# 02-MCU.net
KiCad netlist of a schematic drawn in Altium Designer
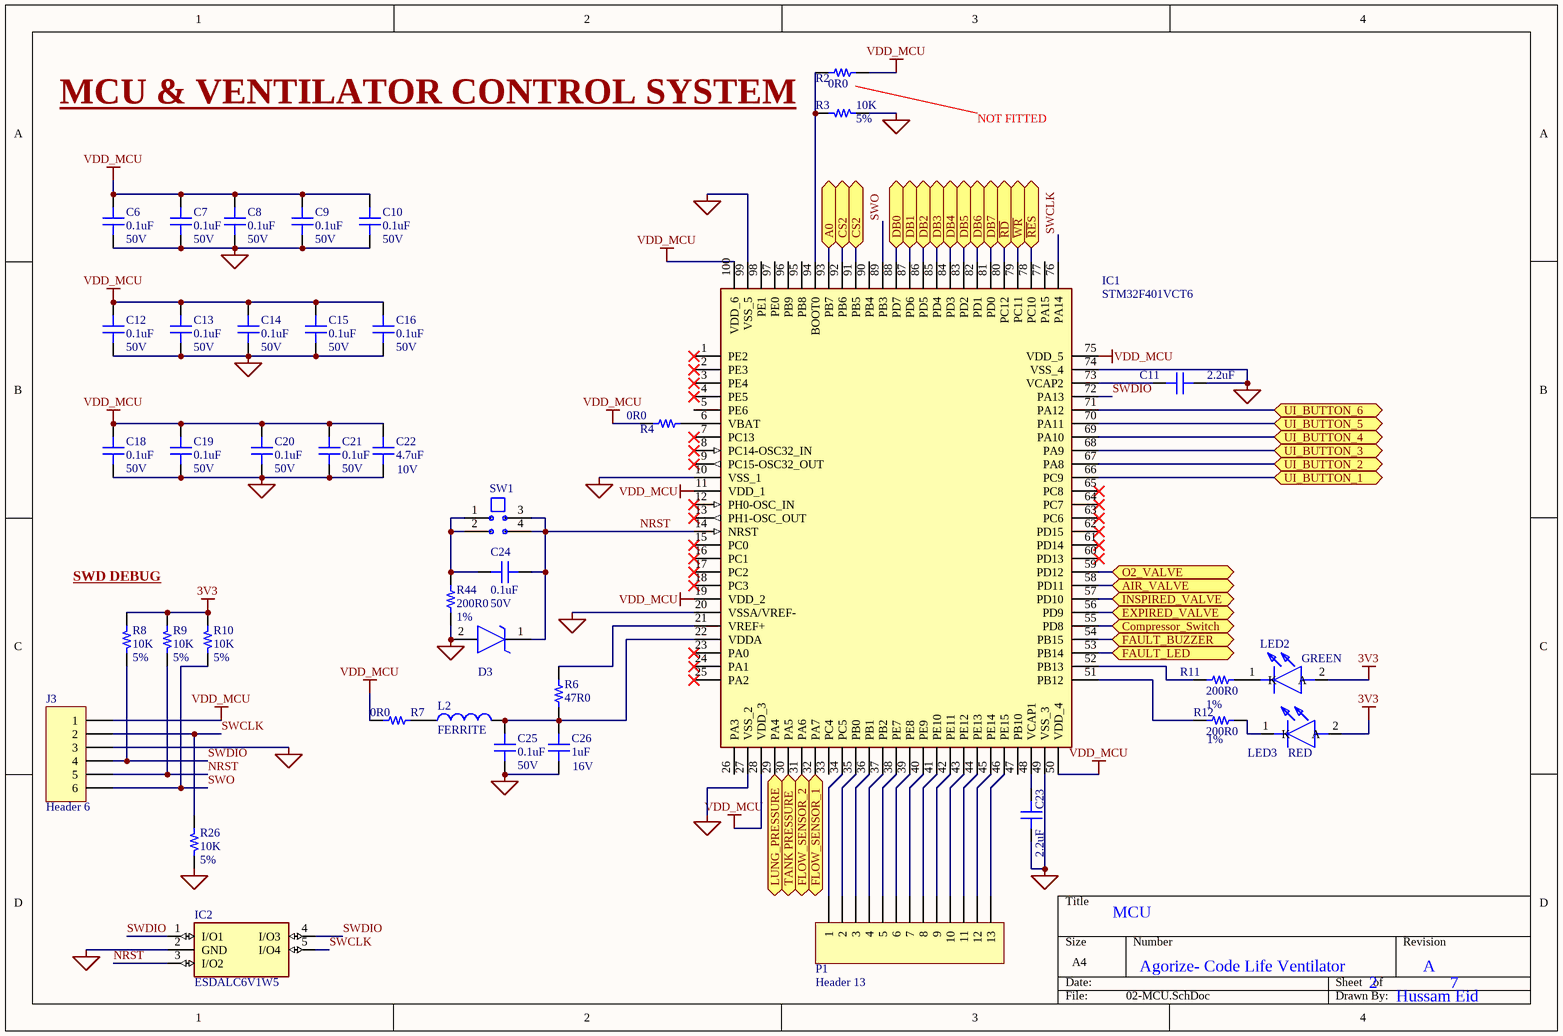
[diagram p0: 02-MCU.SchDoc]

(export (version "E")
  (design (tool "Eeschema 10.0.6"))
  (components
    (comp (ref "C6")
      (value "0.1uF")
      (footprint "CAP 0603/1608")
      (description "CAP CER 0.1UF 50V X7R 0603")
      (fields (field (name "TOLERANCE") "20%") (field (name "VOLTAGE RATING") "50V"))
      (libsource (lib "Celestial Library Database") (part "Capacitor"))
    )
    (comp (ref "C7")
      (value "0.1uF")
      (footprint "CAP 0603/1608")
      (description "CAP CER 0.1UF 50V X7R 0603")
      (fields (field (name "TOLERANCE") "20%") (field (name "VOLTAGE RATING") "50V"))
      (libsource (lib "Celestial Library Database") (part "Capacitor"))
    )
    (comp (ref "C8")
      (value "0.1uF")
      (footprint "CAP 0603/1608")
      (description "CAP CER 0.1UF 50V X7R 0603")
      (fields (field (name "TOLERANCE") "20%") (field (name "VOLTAGE RATING") "50V"))
      (libsource (lib "Celestial Library Database") (part "Capacitor"))
    )
    (comp (ref "C9")
      (value "0.1uF")
      (footprint "CAP 0603/1608")
      (description "CAP CER 0.1UF 50V X7R 0603")
      (fields (field (name "TOLERANCE") "20%") (field (name "VOLTAGE RATING") "50V"))
      (libsource (lib "Celestial Library Database") (part "Capacitor"))
    )
    (comp (ref "C10")
      (value "0.1uF")
      (footprint "CAP 0603/1608")
      (description "CAP CER 0.1UF 50V X7R 0603")
      (fields (field (name "TOLERANCE") "20%") (field (name "VOLTAGE RATING") "50V"))
      (libsource (lib "Celestial Library Database") (part "Capacitor"))
    )
    (comp (ref "C11")
      (value "2.2uF")
      (footprint "CAP 0603/1608")
      (description "CAP CER 2.2UF 16V X5R 0603")
      (fields (field (name "TOLERANCE") "10%") (field (name "VOLTAGE") "16V"))
      (libsource (lib "Celestial Library Database") (part "Capacitor"))
    )
    (comp (ref "C12")
      (value "0.1uF")
      (footprint "CAP 0603/1608")
      (description "CAP CER 0.1UF 50V X7R 0603")
      (fields (field (name "TOLERANCE") "20%") (field (name "VOLTAGE RATING") "50V"))
      (libsource (lib "Celestial Library Database") (part "Capacitor"))
    )
    (comp (ref "C13")
      (value "0.1uF")
      (footprint "CAP 0603/1608")
      (description "CAP CER 0.1UF 50V X7R 0603")
      (fields (field (name "TOLERANCE") "20%") (field (name "VOLTAGE RATING") "50V"))
      (libsource (lib "Celestial Library Database") (part "Capacitor"))
    )
    (comp (ref "C14")
      (value "0.1uF")
      (footprint "CAP 0603/1608")
      (description "CAP CER 0.1UF 50V X7R 0603")
      (fields (field (name "TOLERANCE") "20%") (field (name "VOLTAGE RATING") "50V"))
      (libsource (lib "Celestial Library Database") (part "Capacitor"))
    )
    (comp (ref "C15")
      (value "0.1uF")
      (footprint "CAP 0603/1608")
      (description "CAP CER 0.1UF 50V X7R 0603")
      (fields (field (name "TOLERANCE") "20%") (field (name "VOLTAGE RATING") "50V"))
      (libsource (lib "Celestial Library Database") (part "Capacitor"))
    )
    (comp (ref "C16")
      (value "0.1uF")
      (footprint "CAP 0603/1608")
      (description "CAP CER 0.1UF 50V X7R 0603")
      (fields (field (name "TOLERANCE") "20%") (field (name "VOLTAGE RATING") "50V"))
      (libsource (lib "Celestial Library Database") (part "Capacitor"))
    )
    (comp (ref "C18")
      (value "0.1uF")
      (footprint "CAP 0603/1608")
      (description "CAP CER 0.1UF 50V X7R 0603")
      (fields (field (name "TOLERANCE") "20%") (field (name "VOLTAGE RATING") "50V"))
      (libsource (lib "Celestial Library Database") (part "Capacitor"))
    )
    (comp (ref "C19")
      (value "0.1uF")
      (footprint "CAP 0603/1608")
      (description "CAP CER 0.1UF 50V X7R 0603")
      (fields (field (name "TOLERANCE") "20%") (field (name "VOLTAGE RATING") "50V"))
      (libsource (lib "Celestial Library Database") (part "Capacitor"))
    )
    (comp (ref "C20")
      (value "0.1uF")
      (footprint "CAP 0603/1608")
      (description "CAP CER 0.1UF 50V X7R 0603")
      (fields (field (name "TOLERANCE") "20%") (field (name "VOLTAGE RATING") "50V"))
      (libsource (lib "Celestial Library Database") (part "Capacitor"))
    )
    (comp (ref "C21")
      (value "0.1uF")
      (footprint "CAP 0603/1608")
      (description "CAP CER 0.1UF 50V X7R 0603")
      (fields (field (name "TOLERANCE") "20%") (field (name "VOLTAGE RATING") "50V"))
      (libsource (lib "Celestial Library Database") (part "Capacitor"))
    )
    (comp (ref "C22")
      (value "4.7uF")
      (footprint "CAP 0603/1608")
      (description "CAP CER 4.7UF 10V X5R 0603")
      (fields (field (name "TOLERANCE") "10%") (field (name "VOLTAGE RATING") "10V"))
      (libsource (lib "Celestial Library Database") (part "Capacitor"))
    )
    (comp (ref "C23")
      (value "2.2uF")
      (footprint "CAP 0603/1608")
      (description "CAP CER 2.2UF 16V X5R 0603")
      (fields (field (name "TOLERANCE") "10%") (field (name "VOLTAGE") "16V"))
      (libsource (lib "Celestial Library Database") (part "Capacitor"))
    )
    (comp (ref "C24")
      (value "0.1uF")
      (footprint "CAP 0603/1608")
      (description "CAP CER 0.1UF 50V X7R 0603")
      (fields (field (name "TOLERANCE") "20%") (field (name "VOLTAGE RATING") "50V"))
      (libsource (lib "Celestial Library Database") (part "Capacitor"))
    )
    (comp (ref "C25")
      (value "0.1uF")
      (footprint "CAP 0603/1608")
      (description "CAP CER 0.1UF 50V X7R 0603")
      (fields (field (name "TOLERANCE") "20%") (field (name "VOLTAGE RATING") "50V"))
      (libsource (lib "Celestial Library Database") (part "Capacitor"))
    )
    (comp (ref "C26")
      (value "1uF")
      (footprint "CAP 0603/1608")
      (description "CAP CER 1UF 16V X7R 0603")
      (fields (field (name "TOLERANCE") "20%") (field (name "VOLTAGE RATING (DC)") "16V"))
      (libsource (lib "Celestial Library Database") (part "Capacitor"))
    )
    (comp (ref "D3")
      (value "ESDALC6V1-1U2")
      (footprint "SamacSys:ESDALC6V11U2")
      (description "TVS Diode (Uni-directional)")
      (fields
        (field (name "MOUSER PART NUMBER") "511-ESDALC6V1-1U2")
        (field (name "RS PART NUMBER") "7958404P")
      )
      (libsource (lib "*") (part "ESDALC6V1-1U2"))
    )
    (comp (ref "IC1")
      (value "STM32F401VCT6")
      (footprint "SamacSys:QFP50P1600X1600X160-100N")
      (description "ARM® Cortex®-M4 STM32F4 Microcontroller IC 32-Bit 84MHz 256KB (256K x 8) FLASH 100-LQFP (14x14)")
      (fields
        (field (name "MOUSER PART NUMBER") "511-STM32F401VCT6")
        (field (name "RS PART NUMBER") "7926019P")
      )
      (libsource (lib "*") (part "STM32F401VCT6"))
    )
    (comp (ref "IC2")
      (value "ESDALC6V1W5")
      (footprint "SamacSys:SOT65P210X110-5N")
      (description "Clamp  Ipp Tvs Diode Surface Mount SOT-323-5")
      (fields (field (name "MOUSER PART NUMBER") "511-ESDALC6V1W5") (field (name "RS PART NUMBER") "1787373"))
      (libsource (lib "*") (part "ESDALC6V1W5"))
    )
    (comp (ref "J3")
      (value "Header 6")
      (footprint "HDR1X6")
      (description "Header, 6-Pin")
      (fields (field (name "PUBLISHER") "Altium Limited"))
      (libsource (lib "Miscellaneous Connectors") (part "Header 6"))
    )
    (comp (ref "L2")
      (value "FERRITE")
      (footprint "BEADC1608X95N")
      (description "FERRITE BEAD 300 OHM 0603 1LN")
      (fields (field (name "TOLERANCE") "25%"))
      (libsource (lib "Miscellaneous Devices") (part "Inductor"))
    )
    (comp (ref "LED2")
      (value "GREEN")
      (footprint "SamacSys:150060GS73220")
      (description "LED GREEN CLEAR 0603 SMD")
      (libsource (lib "*") (part "150060GS73220"))
    )
    (comp (ref "LED3")
      (value "RED")
      (footprint "SamacSys:150060GS73220")
      (description "LED GREEN CLEAR 0603 SMD")
      (libsource (lib "*") (part "150060GS73220"))
    )
    (comp (ref "P1")
      (value "Header 13")
      (footprint "HDR1X13")
      (description "Header, 13-Pin")
      (fields (field (name "PUBLISHER") "Altium Limited"))
      (libsource (lib "Miscellaneous Connectors") (part "Header 13"))
    )
    (comp (ref "R2")
      (value "0R0")
      (footprint "RES 0603/1608")
      (description "RES SMD 0 OHM JUMPER 1/10W 0603")
      (fields (field (name "TOLERANCE") "0%"))
      (libsource (lib "Celestial Library Database") (part "Resistor"))
    )
    (comp (ref "R3")
      (value "10K")
      (footprint "RES 0603/1608")
      (description "RES SMD 10K OHM 5% 1/10W 0603")
      (fields (field (name "TOLERANCE") "5%"))
      (libsource (lib "Celestial Library Database") (part "Resistor"))
    )
    (comp (ref "R4")
      (value "0R0")
      (footprint "RES 0603/1608")
      (description "RES SMD 0 OHM JUMPER 1/10W 0603")
      (fields (field (name "TOLERANCE") "0%"))
      (libsource (lib "Celestial Library Database") (part "Resistor"))
    )
    (comp (ref "R6")
      (value "47R0")
      (footprint "RES 0603/1608")
      (description "RESISTOR 47 Ohms ±5% 0.1W, 1/10W Chip Resistor 0603")
      (libsource (lib "Celestial Library Database") (part "Resistor"))
    )
    (comp (ref "R7")
      (value "0R0")
      (footprint "RES 0603/1608")
      (description "RES SMD 0 OHM JUMPER 1/10W 0603")
      (fields (field (name "TOLERANCE") "0%"))
      (libsource (lib "Celestial Library Database") (part "Resistor"))
    )
    (comp (ref "R8")
      (value "10K")
      (footprint "RES 0603/1608")
      (description "RES SMD 10K OHM 5% 1/10W 0603")
      (fields (field (name "TOLERANCE") "5%"))
      (libsource (lib "Celestial Library Database") (part "Resistor"))
    )
    (comp (ref "R9")
      (value "10K")
      (footprint "RES 0603/1608")
      (description "RES SMD 10K OHM 5% 1/10W 0603")
      (fields (field (name "TOLERANCE") "5%"))
      (libsource (lib "Celestial Library Database") (part "Resistor"))
    )
    (comp (ref "R10")
      (value "10K")
      (footprint "RES 0603/1608")
      (description "RES SMD 10K OHM 5% 1/10W 0603")
      (fields (field (name "TOLERANCE") "5%"))
      (libsource (lib "Celestial Library Database") (part "Resistor"))
    )
    (comp (ref "R11")
      (value "200R0")
      (footprint "RES 1206/3216")
      (description "RES SMD 10K OHM 1% 1/4W 1206")
      (fields (field (name "TOLERANCE") "1%"))
      (libsource (lib "Celestial Library Database") (part "Resistor"))
    )
    (comp (ref "R12")
      (value "200R0")
      (footprint "RES 1206/3216")
      (description "RES SMD 10K OHM 1% 1/4W 1206")
      (fields (field (name "TOLERANCE") "1%"))
      (libsource (lib "Celestial Library Database") (part "Resistor"))
    )
    (comp (ref "R26")
      (value "10K")
      (footprint "RES 0603/1608")
      (description "RES SMD 10K OHM 5% 1/10W 0603")
      (fields (field (name "TOLERANCE") "5%"))
      (libsource (lib "Celestial Library Database") (part "Resistor"))
    )
    (comp (ref "R44")
      (value "200R0")
      (footprint "RES 1206/3216")
      (description "RES SMD 10K OHM 1% 1/4W 1206")
      (fields (field (name "TOLERANCE") "1%"))
      (libsource (lib "Celestial Library Database") (part "Resistor"))
    )
    (comp (ref "SW1")
      (value "Tactle switch")
      (footprint "PTS526SM15SMTR2LFS")
      (description "Tactile Switch SPST-NO Top Actuated Surface Mount")
      (libsource (lib "Schlib1") (part "Tactle switch"))
    )
  )
  (nets
    (net (code "1") (name "/A0") (class "Default")
      (node (ref "IC1") (pin "93") (pinfunction "PB7_93") (pintype "passive"))
    )
    (net (code "2") (name "/AIR_VALVE") (class "Default")
      (node (ref "IC1") (pin "58") (pinfunction "PD11_58") (pintype "passive"))
    )
    (net (code "3") (name "/CS2") (class "Default")
      (node (ref "IC1") (pin "91") (pinfunction "PB5_91") (pintype "passive"))
      (node (ref "IC1") (pin "92") (pinfunction "PB6_92") (pintype "passive"))
    )
    (net (code "4") (name "/Compressor_Switch") (class "Default")
      (node (ref "IC1") (pin "55") (pinfunction "PD8_55") (pintype "passive"))
    )
    (net (code "5") (name "/DB0") (class "Default")
      (node (ref "IC1") (pin "88") (pinfunction "PD7_88") (pintype "passive"))
    )
    (net (code "6") (name "/DB1") (class "Default")
      (node (ref "IC1") (pin "87") (pinfunction "PD6_87") (pintype "passive"))
    )
    (net (code "7") (name "/DB2") (class "Default")
      (node (ref "IC1") (pin "86") (pinfunction "PD5_86") (pintype "passive"))
    )
    (net (code "8") (name "/DB3") (class "Default")
      (node (ref "IC1") (pin "85") (pinfunction "PD4_85") (pintype "passive"))
    )
    (net (code "9") (name "/DB4") (class "Default")
      (node (ref "IC1") (pin "84") (pinfunction "PD3_84") (pintype "passive"))
    )
    (net (code "10") (name "/DB5") (class "Default")
      (node (ref "IC1") (pin "83") (pinfunction "PD2_83") (pintype "passive"))
    )
    (net (code "11") (name "/DB6") (class "Default")
      (node (ref "IC1") (pin "82") (pinfunction "PD1_82") (pintype "passive"))
    )
    (net (code "12") (name "/DB7") (class "Default")
      (node (ref "IC1") (pin "81") (pinfunction "PD0_81") (pintype "passive"))
    )
    (net (code "13") (name "/EXPIRED_VALVE") (class "Default")
      (node (ref "IC1") (pin "56") (pinfunction "PD9_56") (pintype "passive"))
    )
    (net (code "14") (name "/FAULT_BUZZER") (class "Default")
      (node (ref "IC1") (pin "54") (pinfunction "PB15_54") (pintype "passive"))
    )
    (net (code "15") (name "/FAULT_LED") (class "Default")
      (node (ref "IC1") (pin "53") (pinfunction "PB14_53") (pintype "passive"))
    )
    (net (code "16") (name "/FLOW_SENSOR_1") (class "Default")
      (node (ref "IC1") (pin "32") (pinfunction "PA7_32") (pintype "passive"))
    )
    (net (code "17") (name "/FLOW_SENSOR_2") (class "Default")
      (node (ref "IC1") (pin "31") (pinfunction "PA6_31") (pintype "passive"))
    )
    (net (code "18") (name "/INSPIRED_VALVE") (class "Default")
      (node (ref "IC1") (pin "57") (pinfunction "PD10_57") (pintype "passive"))
    )
    (net (code "19") (name "/LUNG_PRESSURE") (class "Default")
      (node (ref "IC1") (pin "29") (pinfunction "PA4_29") (pintype "passive"))
    )
    (net (code "20") (name "/NRST") (class "Default")
      (node (ref "C24") (pin "2") (pinfunction "2_2") (pintype "passive"))
      (node (ref "D3") (pin "1") (pinfunction "K_1") (pintype "passive"))
      (node (ref "IC1") (pin "14") (pinfunction "NRST_14") (pintype "input"))
      (node (ref "IC2") (pin "3") (pinfunction "I/O2_3") (pintype "bidirectional"))
      (node (ref "J3") (pin "5") (pinfunction "5_5") (pintype "passive"))
      (node (ref "R9") (pin "2") (pinfunction "2_2") (pintype "passive"))
      (node (ref "SW1") (pin "3") (pinfunction "3_3") (pintype "passive"))
      (node (ref "SW1") (pin "4") (pinfunction "4_4") (pintype "passive"))
    )
    (net (code "21") (name "/O2_VALVE") (class "Default")
      (node (ref "IC1") (pin "59") (pinfunction "PD12_59") (pintype "passive"))
    )
    (net (code "22") (name "/SWCLK") (class "Default")
      (node (ref "IC1") (pin "76") (pinfunction "PA14_76") (pintype "passive"))
      (node (ref "IC2") (pin "5") (pinfunction "I/O4_5") (pintype "bidirectional"))
      (node (ref "J3") (pin "2") (pinfunction "2_2") (pintype "passive"))
      (node (ref "R26") (pin "2") (pinfunction "2_2") (pintype "passive"))
    )
    (net (code "23") (name "/SWDIO") (class "Default")
      (node (ref "IC1") (pin "72") (pinfunction "PA13_72") (pintype "passive"))
      (node (ref "IC2") (pin "1") (pinfunction "I/O1_1") (pintype "bidirectional"))
      (node (ref "IC2") (pin "4") (pinfunction "I/O3_4") (pintype "bidirectional"))
      (node (ref "J3") (pin "4") (pinfunction "4_4") (pintype "passive"))
      (node (ref "R8") (pin "2") (pinfunction "2_2") (pintype "passive"))
    )
    (net (code "24") (name "/SWO") (class "Default")
      (node (ref "IC1") (pin "89") (pinfunction "PB3_89") (pintype "passive"))
      (node (ref "J3") (pin "6") (pinfunction "6_6") (pintype "passive"))
      (node (ref "R10") (pin "2") (pinfunction "2_2") (pintype "passive"))
    )
    (net (code "25") (name "/TANK PRESSURE") (class "Default")
      (node (ref "IC1") (pin "30") (pinfunction "PA5_30") (pintype "passive"))
    )
    (net (code "26") (name "/UI_BUTTON_1") (class "Default")
      (node (ref "IC1") (pin "66") (pinfunction "PC9_66") (pintype "passive"))
    )
    (net (code "27") (name "/UI_BUTTON_2") (class "Default")
      (node (ref "IC1") (pin "67") (pinfunction "PA8_67") (pintype "passive"))
    )
    (net (code "28") (name "/UI_BUTTON_3") (class "Default")
      (node (ref "IC1") (pin "68") (pinfunction "PA9_68") (pintype "passive"))
    )
    (net (code "29") (name "/UI_BUTTON_4") (class "Default")
      (node (ref "IC1") (pin "69") (pinfunction "PA10_69") (pintype "passive"))
    )
    (net (code "30") (name "/UI_BUTTON_5") (class "Default")
      (node (ref "IC1") (pin "70") (pinfunction "PA11_70") (pintype "passive"))
    )
    (net (code "31") (name "/UI_BUTTON_6") (class "Default")
      (node (ref "IC1") (pin "71") (pinfunction "PA12_71") (pintype "passive"))
    )
    (net (code "32") (name "/~{RD}") (class "Default")
      (node (ref "IC1") (pin "80") (pinfunction "PC12_80") (pintype "passive"))
    )
    (net (code "33") (name "/~{RE}S") (class "Default")
      (node (ref "IC1") (pin "78") (pinfunction "PC10_78") (pintype "passive"))
    )
    (net (code "34") (name "/~{WR}") (class "Default")
      (node (ref "IC1") (pin "79") (pinfunction "PC11_79") (pintype "passive"))
    )
    (net (code "35") (name "3V3") (class "Default")
      (node (ref "LED2") (pin "2") (pinfunction "A_2") (pintype "passive"))
      (node (ref "LED3") (pin "2") (pinfunction "A_2") (pintype "passive"))
      (node (ref "R10") (pin "1") (pinfunction "1_1") (pintype "passive"))
      (node (ref "R8") (pin "1") (pinfunction "1_1") (pintype "passive"))
      (node (ref "R9") (pin "1") (pinfunction "1_1") (pintype "passive"))
    )
    (net (code "36") (name "COM") (class "Default")
      (node (ref "C10") (pin "2") (pinfunction "2_2") (pintype "passive"))
      (node (ref "C11") (pin "2") (pinfunction "2_2") (pintype "passive"))
      (node (ref "C12") (pin "2") (pinfunction "2_2") (pintype "passive"))
      (node (ref "C13") (pin "2") (pinfunction "2_2") (pintype "passive"))
      (node (ref "C14") (pin "2") (pinfunction "2_2") (pintype "passive"))
      (node (ref "C15") (pin "2") (pinfunction "2_2") (pintype "passive"))
      (node (ref "C16") (pin "2") (pinfunction "2_2") (pintype "passive"))
      (node (ref "C18") (pin "2") (pinfunction "2_2") (pintype "passive"))
      (node (ref "C19") (pin "2") (pinfunction "2_2") (pintype "passive"))
      (node (ref "C20") (pin "2") (pinfunction "2_2") (pintype "passive"))
      (node (ref "C21") (pin "2") (pinfunction "2_2") (pintype "passive"))
      (node (ref "C22") (pin "2") (pinfunction "2_2") (pintype "passive"))
      (node (ref "C23") (pin "1") (pinfunction "1_1") (pintype "passive"))
      (node (ref "C25") (pin "2") (pinfunction "2_2") (pintype "passive"))
      (node (ref "C26") (pin "2") (pinfunction "2_2") (pintype "passive"))
      (node (ref "C6") (pin "2") (pinfunction "2_2") (pintype "passive"))
      (node (ref "C7") (pin "2") (pinfunction "2_2") (pintype "passive"))
      (node (ref "C8") (pin "2") (pinfunction "2_2") (pintype "passive"))
      (node (ref "C9") (pin "2") (pinfunction "2_2") (pintype "passive"))
      (node (ref "D3") (pin "2") (pinfunction "A_2") (pintype "passive"))
      (node (ref "IC1") (pin "10") (pinfunction "VSS_1_10") (pintype "power_in"))
      (node (ref "IC1") (pin "20") (pinfunction "VSSA/VREF-_20") (pintype "power_in"))
      (node (ref "IC1") (pin "27") (pinfunction "VSS_2_27") (pintype "power_in"))
      (node (ref "IC1") (pin "49") (pinfunction "VSS_3_49") (pintype "power_in"))
      (node (ref "IC1") (pin "74") (pinfunction "VSS_4_74") (pintype "power_in"))
      (node (ref "IC1") (pin "99") (pinfunction "VSS_5_99") (pintype "power_in"))
      (node (ref "IC2") (pin "2") (pinfunction "GND_2") (pintype "power_in"))
      (node (ref "J3") (pin "3") (pinfunction "3_3") (pintype "passive"))
      (node (ref "R26") (pin "1") (pinfunction "1_1") (pintype "passive"))
      (node (ref "R3") (pin "1") (pinfunction "1_1") (pintype "passive"))
      (node (ref "R44") (pin "1") (pinfunction "1_1") (pintype "passive"))
    )
    (net (code "37") (name "Net-(C24-Pad1)") (class "Default")
      (node (ref "C24") (pin "1") (pinfunction "1_1") (pintype "passive"))
      (node (ref "R44") (pin "2") (pinfunction "2_2") (pintype "passive"))
      (node (ref "SW1") (pin "1") (pinfunction "1_1") (pintype "passive"))
      (node (ref "SW1") (pin "2") (pinfunction "2_2") (pintype "passive"))
    )
    (net (code "38") (name "Net-(IC1-BOOT0)") (class "Default")
      (node (ref "IC1") (pin "94") (pinfunction "BOOT0_94") (pintype "passive"))
      (node (ref "R2") (pin "1") (pinfunction "1_1") (pintype "passive"))
      (node (ref "R3") (pin "2") (pinfunction "2_2") (pintype "passive"))
    )
    (net (code "39") (name "Net-(IC1-PB0)") (class "Default")
      (node (ref "IC1") (pin "35") (pinfunction "PB0_35") (pintype "passive"))
      (node (ref "P1") (pin "2") (pinfunction "2_2") (pintype "passive"))
    )
    (net (code "40") (name "Net-(IC1-PB1)") (class "Default")
      (node (ref "IC1") (pin "36") (pinfunction "PB1_36") (pintype "passive"))
      (node (ref "P1") (pin "3") (pinfunction "3_3") (pintype "passive"))
    )
    (net (code "41") (name "Net-(IC1-PB2)") (class "Default")
      (node (ref "IC1") (pin "37") (pinfunction "PB2_37") (pintype "passive"))
      (node (ref "P1") (pin "4") (pinfunction "4_4") (pintype "passive"))
    )
    (net (code "42") (name "Net-(IC1-PB12)") (class "Default")
      (node (ref "IC1") (pin "51") (pinfunction "PB12_51") (pintype "passive"))
      (node (ref "R12") (pin "1") (pinfunction "1_1") (pintype "passive"))
    )
    (net (code "43") (name "Net-(IC1-PB13)") (class "Default")
      (node (ref "IC1") (pin "52") (pinfunction "PB13_52") (pintype "passive"))
      (node (ref "R11") (pin "1") (pinfunction "1_1") (pintype "passive"))
    )
    (net (code "44") (name "Net-(IC1-PC5)") (class "Default")
      (node (ref "IC1") (pin "34") (pinfunction "PC5_34") (pintype "passive"))
      (node (ref "P1") (pin "1") (pinfunction "1_1") (pintype "passive"))
    )
    (net (code "45") (name "Net-(IC1-PE7)") (class "Default")
      (node (ref "IC1") (pin "38") (pinfunction "PE7_38") (pintype "passive"))
      (node (ref "P1") (pin "5") (pinfunction "5_5") (pintype "passive"))
    )
    (net (code "46") (name "Net-(IC1-PE8)") (class "Default")
      (node (ref "IC1") (pin "39") (pinfunction "PE8_39") (pintype "passive"))
      (node (ref "P1") (pin "6") (pinfunction "6_6") (pintype "passive"))
    )
    (net (code "47") (name "Net-(IC1-PE9)") (class "Default")
      (node (ref "IC1") (pin "40") (pinfunction "PE9_40") (pintype "passive"))
      (node (ref "P1") (pin "7") (pinfunction "7_7") (pintype "passive"))
    )
    (net (code "48") (name "Net-(IC1-PE10)") (class "Default")
      (node (ref "IC1") (pin "41") (pinfunction "PE10_41") (pintype "passive"))
      (node (ref "P1") (pin "8") (pinfunction "8_8") (pintype "passive"))
    )
    (net (code "49") (name "Net-(IC1-PE11)") (class "Default")
      (node (ref "IC1") (pin "42") (pinfunction "PE11_42") (pintype "passive"))
      (node (ref "P1") (pin "9") (pinfunction "9_9") (pintype "passive"))
    )
    (net (code "50") (name "Net-(IC1-PE12)") (class "Default")
      (node (ref "IC1") (pin "43") (pinfunction "PE12_43") (pintype "passive"))
      (node (ref "P1") (pin "10") (pinfunction "10_10") (pintype "passive"))
    )
    (net (code "51") (name "Net-(IC1-PE13)") (class "Default")
      (node (ref "IC1") (pin "44") (pinfunction "PE13_44") (pintype "passive"))
      (node (ref "P1") (pin "11") (pinfunction "11_11") (pintype "passive"))
    )
    (net (code "52") (name "Net-(IC1-PE14)") (class "Default")
      (node (ref "IC1") (pin "45") (pinfunction "PE14_45") (pintype "passive"))
      (node (ref "P1") (pin "12") (pinfunction "12_12") (pintype "passive"))
    )
    (net (code "53") (name "Net-(IC1-PE15)") (class "Default")
      (node (ref "IC1") (pin "46") (pinfunction "PE15_46") (pintype "passive"))
      (node (ref "P1") (pin "13") (pinfunction "13_13") (pintype "passive"))
    )
    (net (code "54") (name "Net-(IC1-VBAT)") (class "Default")
      (node (ref "IC1") (pin "6") (pinfunction "VBAT_6") (pintype "passive"))
      (node (ref "R4") (pin "2") (pinfunction "2_2") (pintype "passive"))
    )
    (net (code "55") (name "Net-(IC1-VCAP1)") (class "Default")
      (node (ref "C23") (pin "2") (pinfunction "2_2") (pintype "passive"))
      (node (ref "IC1") (pin "48") (pinfunction "VCAP1_48") (pintype "passive"))
    )
    (net (code "56") (name "Net-(IC1-VCAP2)") (class "Default")
      (node (ref "C11") (pin "1") (pinfunction "1_1") (pintype "passive"))
      (node (ref "IC1") (pin "73") (pinfunction "VCAP2_73") (pintype "passive"))
    )
    (net (code "57") (name "Net-(IC1-VDDA)") (class "Default")
      (node (ref "C25") (pin "1") (pinfunction "1_1") (pintype "passive"))
      (node (ref "C26") (pin "1") (pinfunction "1_1") (pintype "passive"))
      (node (ref "IC1") (pin "22") (pinfunction "VDDA_22") (pintype "power_in"))
      (node (ref "L2") (pin "2") (pinfunction "2_2") (pintype "passive"))
      (node (ref "R6") (pin "1") (pinfunction "1_1") (pintype "passive"))
    )
    (net (code "58") (name "Net-(IC1-VREF+)") (class "Default")
      (node (ref "IC1") (pin "21") (pinfunction "VREF+_21") (pintype "passive"))
      (node (ref "R6") (pin "2") (pinfunction "2_2") (pintype "passive"))
    )
    (net (code "59") (name "Net-(L2-Pad1)") (class "Default")
      (node (ref "L2") (pin "1") (pinfunction "1_1") (pintype "passive"))
      (node (ref "R7") (pin "2") (pinfunction "2_2") (pintype "passive"))
    )
    (net (code "60") (name "Net-(LED2-K)") (class "Default")
      (node (ref "LED2") (pin "1") (pinfunction "K_1") (pintype "passive"))
      (node (ref "R11") (pin "2") (pinfunction "2_2") (pintype "passive"))
    )
    (net (code "61") (name "Net-(LED3-K)") (class "Default")
      (node (ref "LED3") (pin "1") (pinfunction "K_1") (pintype "passive"))
      (node (ref "R12") (pin "2") (pinfunction "2_2") (pintype "passive"))
    )
    (net (code "62") (name "VDD_MCU") (class "Default")
      (node (ref "C10") (pin "1") (pinfunction "1_1") (pintype "passive"))
      (node (ref "C12") (pin "1") (pinfunction "1_1") (pintype "passive"))
      (node (ref "C13") (pin "1") (pinfunction "1_1") (pintype "passive"))
      (node (ref "C14") (pin "1") (pinfunction "1_1") (pintype "passive"))
      (node (ref "C15") (pin "1") (pinfunction "1_1") (pintype "passive"))
      (node (ref "C16") (pin "1") (pinfunction "1_1") (pintype "passive"))
      (node (ref "C18") (pin "1") (pinfunction "1_1") (pintype "passive"))
      (node (ref "C19") (pin "1") (pinfunction "1_1") (pintype "passive"))
      (node (ref "C20") (pin "1") (pinfunction "1_1") (pintype "passive"))
      (node (ref "C21") (pin "1") (pinfunction "1_1") (pintype "passive"))
      (node (ref "C22") (pin "1") (pinfunction "1_1") (pintype "passive"))
      (node (ref "C6") (pin "1") (pinfunction "1_1") (pintype "passive"))
      (node (ref "C7") (pin "1") (pinfunction "1_1") (pintype "passive"))
      (node (ref "C8") (pin "1") (pinfunction "1_1") (pintype "passive"))
      (node (ref "C9") (pin "1") (pinfunction "1_1") (pintype "passive"))
      (node (ref "IC1") (pin "100") (pinfunction "VDD_6_100") (pintype "power_in"))
      (node (ref "IC1") (pin "11") (pinfunction "VDD_1_11") (pintype "power_in"))
      (node (ref "IC1") (pin "19") (pinfunction "VDD_2_19") (pintype "power_in"))
      (node (ref "IC1") (pin "28") (pinfunction "VDD_3_28") (pintype "power_in"))
      (node (ref "IC1") (pin "50") (pinfunction "VDD_4_50") (pintype "power_in"))
      (node (ref "IC1") (pin "75") (pinfunction "VDD_5_75") (pintype "power_in"))
      (node (ref "J3") (pin "1") (pinfunction "1_1") (pintype "passive"))
      (node (ref "R2") (pin "2") (pinfunction "2_2") (pintype "passive"))
      (node (ref "R4") (pin "1") (pinfunction "1_1") (pintype "passive"))
      (node (ref "R7") (pin "1") (pinfunction "1_1") (pintype "passive"))
    )
    (net (code "63") (name "unconnected-(IC1-PA0-Pad23)") (class "Default")
      (node (ref "IC1") (pin "23") (pinfunction "PA0_23") (pintype "passive+no_connect"))
    )
    (net (code "64") (name "unconnected-(IC1-PA1-Pad24)") (class "Default")
      (node (ref "IC1") (pin "24") (pinfunction "PA1_24") (pintype "passive+no_connect"))
    )
    (net (code "65") (name "unconnected-(IC1-PA2-Pad25)") (class "Default")
      (node (ref "IC1") (pin "25") (pinfunction "PA2_25") (pintype "passive+no_connect"))
    )
    (net (code "66") (name "unconnected-(IC1-PA3-Pad26)") (class "Default")
      (node (ref "IC1") (pin "26") (pinfunction "PA3_26") (pintype "passive"))
    )
    (net (code "67") (name "unconnected-(IC1-PA15-Pad77)") (class "Default")
      (node (ref "IC1") (pin "77") (pinfunction "PA15_77") (pintype "passive"))
    )
    (net (code "68") (name "unconnected-(IC1-PB4-Pad90)") (class "Default")
      (node (ref "IC1") (pin "90") (pinfunction "PB4_90") (pintype "passive"))
    )
    (net (code "69") (name "unconnected-(IC1-PB8-Pad95)") (class "Default")
      (node (ref "IC1") (pin "95") (pinfunction "PB8_95") (pintype "passive"))
    )
    (net (code "70") (name "unconnected-(IC1-PB9-Pad96)") (class "Default")
      (node (ref "IC1") (pin "96") (pinfunction "PB9_96") (pintype "passive"))
    )
    (net (code "71") (name "unconnected-(IC1-PB10-Pad47)") (class "Default")
      (node (ref "IC1") (pin "47") (pinfunction "PB10_47") (pintype "passive"))
    )
    (net (code "72") (name "unconnected-(IC1-PC0-Pad15)") (class "Default")
      (node (ref "IC1") (pin "15") (pinfunction "PC0_15") (pintype "passive+no_connect"))
    )
    (net (code "73") (name "unconnected-(IC1-PC1-Pad16)") (class "Default")
      (node (ref "IC1") (pin "16") (pinfunction "PC1_16") (pintype "passive+no_connect"))
    )
    (net (code "74") (name "unconnected-(IC1-PC2-Pad17)") (class "Default")
      (node (ref "IC1") (pin "17") (pinfunction "PC2_17") (pintype "passive+no_connect"))
    )
    (net (code "75") (name "unconnected-(IC1-PC3-Pad18)") (class "Default")
      (node (ref "IC1") (pin "18") (pinfunction "PC3_18") (pintype "passive+no_connect"))
    )
    (net (code "76") (name "unconnected-(IC1-PC4-Pad33)") (class "Default")
      (node (ref "IC1") (pin "33") (pinfunction "PC4_33") (pintype "passive"))
    )
    (net (code "77") (name "unconnected-(IC1-PC6-Pad63)") (class "Default")
      (node (ref "IC1") (pin "63") (pinfunction "PC6_63") (pintype "passive+no_connect"))
    )
    (net (code "78") (name "unconnected-(IC1-PC7-Pad64)") (class "Default")
      (node (ref "IC1") (pin "64") (pinfunction "PC7_64") (pintype "passive+no_connect"))
    )
    (net (code "79") (name "unconnected-(IC1-PC8-Pad65)") (class "Default")
      (node (ref "IC1") (pin "65") (pinfunction "PC8_65") (pintype "passive+no_connect"))
    )
    (net (code "80") (name "unconnected-(IC1-PC13-Pad7)") (class "Default")
      (node (ref "IC1") (pin "7") (pinfunction "PC13_7") (pintype "passive+no_connect"))
    )
    (net (code "81") (name "unconnected-(IC1-PC14-OSC32_IN-Pad8)") (class "Default")
      (node (ref "IC1") (pin "8") (pinfunction "PC14-OSC32_IN_8") (pintype "input+no_connect"))
    )
    (net (code "82") (name "unconnected-(IC1-PC15-OSC32_OUT-Pad9)") (class "Default")
      (node (ref "IC1") (pin "9") (pinfunction "PC15-OSC32_OUT_9") (pintype "output+no_connect"))
    )
    (net (code "83") (name "unconnected-(IC1-PD13-Pad60)") (class "Default")
      (node (ref "IC1") (pin "60") (pinfunction "PD13_60") (pintype "passive+no_connect"))
    )
    (net (code "84") (name "unconnected-(IC1-PD14-Pad61)") (class "Default")
      (node (ref "IC1") (pin "61") (pinfunction "PD14_61") (pintype "passive+no_connect"))
    )
    (net (code "85") (name "unconnected-(IC1-PD15-Pad62)") (class "Default")
      (node (ref "IC1") (pin "62") (pinfunction "PD15_62") (pintype "passive+no_connect"))
    )
    (net (code "86") (name "unconnected-(IC1-PE0-Pad97)") (class "Default")
      (node (ref "IC1") (pin "97") (pinfunction "PE0_97") (pintype "passive"))
    )
    (net (code "87") (name "unconnected-(IC1-PE1-Pad98)") (class "Default")
      (node (ref "IC1") (pin "98") (pinfunction "PE1_98") (pintype "passive"))
    )
    (net (code "88") (name "unconnected-(IC1-PE2-Pad1)") (class "Default")
      (node (ref "IC1") (pin "1") (pinfunction "PE2_1") (pintype "passive+no_connect"))
    )
    (net (code "89") (name "unconnected-(IC1-PE3-Pad2)") (class "Default")
      (node (ref "IC1") (pin "2") (pinfunction "PE3_2") (pintype "passive+no_connect"))
    )
    (net (code "90") (name "unconnected-(IC1-PE4-Pad3)") (class "Default")
      (node (ref "IC1") (pin "3") (pinfunction "PE4_3") (pintype "passive+no_connect"))
    )
    (net (code "91") (name "unconnected-(IC1-PE5-Pad4)") (class "Default")
      (node (ref "IC1") (pin "4") (pinfunction "PE5_4") (pintype "passive+no_connect"))
    )
    (net (code "92") (name "unconnected-(IC1-PE6-Pad5)") (class "Default")
      (node (ref "IC1") (pin "5") (pinfunction "PE6_5") (pintype "passive"))
    )
    (net (code "93") (name "unconnected-(IC1-PH0-OSC_IN-Pad12)") (class "Default")
      (node (ref "IC1") (pin "12") (pinfunction "PH0-OSC_IN_12") (pintype "input+no_connect"))
    )
    (net (code "94") (name "unconnected-(IC1-PH1-OSC_OUT-Pad13)") (class "Default")
      (node (ref "IC1") (pin "13") (pinfunction "PH1-OSC_OUT_13") (pintype "output+no_connect"))
    )
  )
)
